# busfahrer_pi.net
KiCad netlist of a schematic drawn in EAGLE
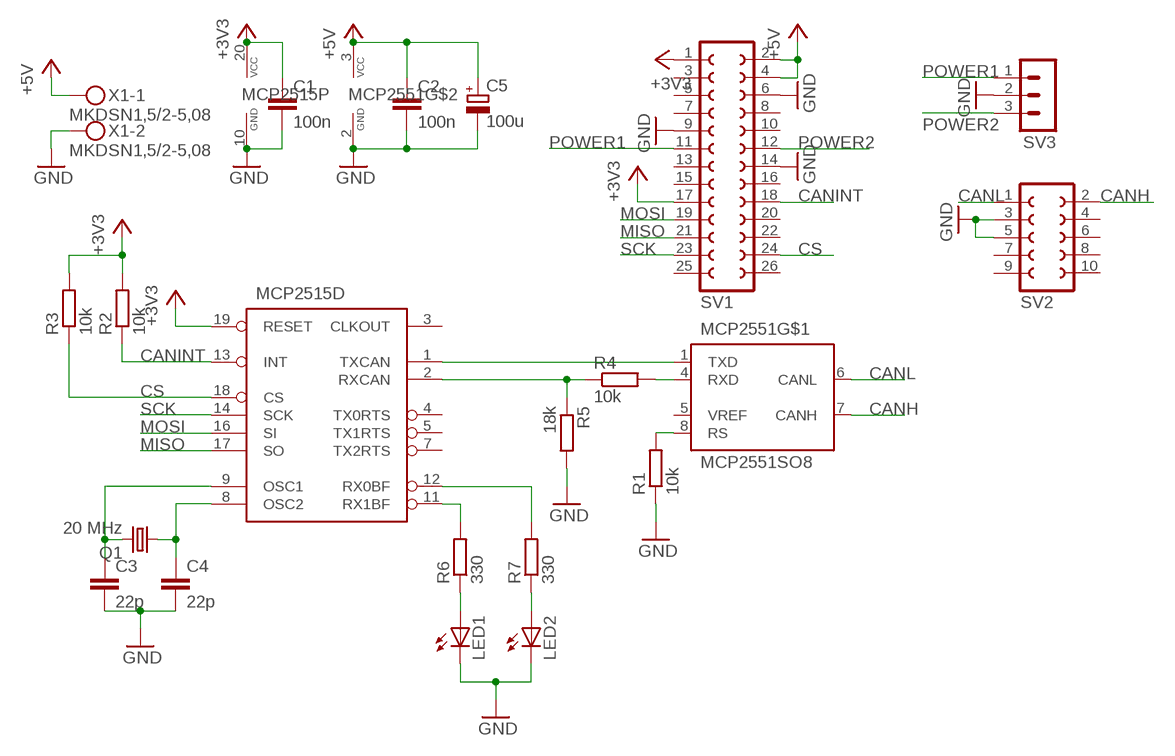
[diagram p0: schematic, sheet 1]

(export (version "E")
  (design (tool "Eeschema 10.0.6"))
  (components
    (comp (ref "C1")
      (value "100n")
      (footprint "eagle-import:C0805")
      (libsource (lib "eagle-import") (part "C-EUC0805"))
    )
    (comp (ref "C2")
      (value "100n")
      (footprint "eagle-import:C0805")
      (libsource (lib "eagle-import") (part "C-EUC0805"))
    )
    (comp (ref "C3")
      (value "22p")
      (footprint "eagle-import:C0805")
      (libsource (lib "eagle-import") (part "C-EUC0805"))
    )
    (comp (ref "C4")
      (value "22p")
      (footprint "eagle-import:C0805")
      (libsource (lib "eagle-import") (part "C-EUC0805"))
    )
    (comp (ref "C5")
      (value "100u")
      (footprint "eagle-import:E2,5-6")
      (libsource (lib "eagle-import") (part "CPOL-EUE2.5-6"))
    )
    (comp (ref "LED1")
      (value "LEDCHIP-LED0805")
      (footprint "eagle-import:CHIP-LED0805")
      (libsource (lib "eagle-import") (part "LEDCHIP-LED0805"))
    )
    (comp (ref "LED2")
      (value "LEDCHIP-LED0805")
      (footprint "eagle-import:CHIP-LED0805")
      (libsource (lib "eagle-import") (part "LEDCHIP-LED0805"))
    )
    (comp (ref "MCP2515")
      (value "MCP2515ST")
      (footprint "eagle-import:TSSOP20")
      (libsource (lib "eagle-import") (part "MCP2515ST"))
    )
    (comp (ref "MCP2551")
      (value "MCP2551SO8")
      (footprint "eagle-import:SO08")
      (libsource (lib "eagle-import") (part "MCP2551SO8"))
    )
    (comp (ref "Q1")
      (value "20 MHz")
      (footprint "eagle-import:HC49_S")
      (libsource (lib "eagle-import") (part "CRYSTALHC49S"))
    )
    (comp (ref "R1")
      (value "10k")
      (footprint "eagle-import:R0805")
      (libsource (lib "eagle-import") (part "R-EU_R0805"))
    )
    (comp (ref "R2")
      (value "10k")
      (footprint "eagle-import:R0805")
      (libsource (lib "eagle-import") (part "R-EU_R0805"))
    )
    (comp (ref "R3")
      (value "10k")
      (footprint "eagle-import:R0805")
      (libsource (lib "eagle-import") (part "R-EU_R0805"))
    )
    (comp (ref "R4")
      (value "10k")
      (footprint "eagle-import:R0805")
      (libsource (lib "eagle-import") (part "rcl_patch_R-EU_R0805"))
    )
    (comp (ref "R5")
      (value "18k")
      (footprint "eagle-import:R0805")
      (libsource (lib "eagle-import") (part "R-EU_R0805"))
    )
    (comp (ref "R6")
      (value "330")
      (footprint "eagle-import:R0805")
      (libsource (lib "eagle-import") (part "R-EU_R0805"))
    )
    (comp (ref "R7")
      (value "330")
      (footprint "eagle-import:R0805")
      (libsource (lib "eagle-import") (part "R-EU_R0805"))
    )
    (comp (ref "SV1")
      (value "FE13-2")
      (footprint "eagle-import:FE13-2")
      (libsource (lib "eagle-import") (part "FE13-2"))
    )
    (comp (ref "SV2")
      (value "FE05-2")
      (footprint "eagle-import:FE05-2")
      (libsource (lib "eagle-import") (part "FE05-2"))
    )
    (comp (ref "SV3")
      (value "MA03-1")
      (footprint "eagle-import:MA03-1")
      (libsource (lib "eagle-import") (part "MA03-1"))
    )
    (comp (ref "X1")
      (value "MKDSN1,5/2-5,08")
      (footprint "eagle-import:MKDSN1,5_2-5,08")
      (fields (field (name "MPN") "MKDSN 1,5/2-5.08"))
      (libsource (lib "eagle-import") (part "MKDSN1,5/2-5,08"))
    )
  )
  (nets
    (net (code "1") (name "+3V3") (class "Default")
      (node (ref "C1") (pin "1") (pinfunction "1_1") (pintype "passive"))
      (node (ref "MCP2515") (pin "19") (pinfunction "RESET_19") (pintype "input"))
      (node (ref "MCP2515") (pin "20") (pinfunction "VCC_20") (pintype "power_in"))
      (node (ref "R2") (pin "2") (pinfunction "2_2") (pintype "passive"))
      (node (ref "R3") (pin "2") (pinfunction "2_2") (pintype "passive"))
      (node (ref "SV1") (pin "1") (pinfunction "1_1") (pintype "passive"))
      (node (ref "SV1") (pin "17") (pinfunction "17_17") (pintype "passive"))
    )
    (net (code "2") (name "+5V") (class "Default")
      (node (ref "C2") (pin "1") (pinfunction "1_1") (pintype "passive"))
      (node (ref "C5") (pin "+") (pinfunction "+_+") (pintype "passive"))
      (node (ref "MCP2551") (pin "3") (pinfunction "VCC_3") (pintype "power_in"))
      (node (ref "SV1") (pin "2") (pinfunction "2_2") (pintype "passive"))
      (node (ref "SV1") (pin "4") (pinfunction "4_4") (pintype "passive"))
      (node (ref "X1") (pin "1") (pinfunction "KL_1") (pintype "passive"))
    )
    (net (code "3") (name "/CANH") (class "Default")
      (node (ref "MCP2551") (pin "7") (pinfunction "CANH_7") (pintype "bidirectional"))
      (node (ref "SV2") (pin "2") (pinfunction "2_2") (pintype "passive"))
    )
    (net (code "4") (name "/CANINT") (class "Default")
      (node (ref "MCP2515") (pin "13") (pinfunction "INT_13") (pintype "output"))
      (node (ref "R2") (pin "1") (pinfunction "1_1") (pintype "passive"))
      (node (ref "SV1") (pin "18") (pinfunction "18_18") (pintype "passive"))
    )
    (net (code "5") (name "/CANL") (class "Default")
      (node (ref "MCP2551") (pin "6") (pinfunction "CANL_6") (pintype "bidirectional"))
      (node (ref "SV2") (pin "1") (pinfunction "1_1") (pintype "passive"))
    )
    (net (code "6") (name "/CS") (class "Default")
      (node (ref "MCP2515") (pin "18") (pinfunction "CS_18") (pintype "input"))
      (node (ref "R3") (pin "1") (pinfunction "1_1") (pintype "passive"))
      (node (ref "SV1") (pin "24") (pinfunction "24_24") (pintype "passive"))
    )
    (net (code "7") (name "/MISO") (class "Default")
      (node (ref "MCP2515") (pin "17") (pinfunction "SO_17") (pintype "output"))
      (node (ref "SV1") (pin "21") (pinfunction "21_21") (pintype "passive"))
    )
    (net (code "8") (name "/MOSI") (class "Default")
      (node (ref "MCP2515") (pin "16") (pinfunction "SI_16") (pintype "input"))
      (node (ref "SV1") (pin "19") (pinfunction "19_19") (pintype "passive"))
    )
    (net (code "9") (name "/POWER1") (class "Default")
      (node (ref "SV1") (pin "11") (pinfunction "11_11") (pintype "passive"))
      (node (ref "SV3") (pin "1") (pinfunction "1_1") (pintype "passive"))
    )
    (net (code "10") (name "/POWER2") (class "Default")
      (node (ref "SV1") (pin "12") (pinfunction "12_12") (pintype "passive"))
      (node (ref "SV3") (pin "3") (pinfunction "3_3") (pintype "passive"))
    )
    (net (code "11") (name "/SCK") (class "Default")
      (node (ref "MCP2515") (pin "14") (pinfunction "SCK_14") (pintype "input"))
      (node (ref "SV1") (pin "23") (pinfunction "23_23") (pintype "passive"))
    )
    (net (code "12") (name "GND") (class "Default")
      (node (ref "C1") (pin "2") (pinfunction "2_2") (pintype "passive"))
      (node (ref "C2") (pin "2") (pinfunction "2_2") (pintype "passive"))
      (node (ref "C3") (pin "2") (pinfunction "2_2") (pintype "passive"))
      (node (ref "C4") (pin "2") (pinfunction "2_2") (pintype "passive"))
      (node (ref "C5") (pin "-") (pinfunction "-_-") (pintype "passive"))
      (node (ref "LED1") (pin "C") (pinfunction "C_C") (pintype "passive"))
      (node (ref "LED2") (pin "C") (pinfunction "C_C") (pintype "passive"))
      (node (ref "MCP2515") (pin "10") (pinfunction "GND_10") (pintype "power_in"))
      (node (ref "MCP2551") (pin "2") (pinfunction "GND_2") (pintype "power_in"))
      (node (ref "R1") (pin "1") (pinfunction "1_1") (pintype "passive"))
      (node (ref "R5") (pin "2") (pinfunction "2_2") (pintype "passive"))
      (node (ref "SV1") (pin "14") (pinfunction "14_14") (pintype "passive"))
      (node (ref "SV1") (pin "6") (pinfunction "6_6") (pintype "passive"))
      (node (ref "SV1") (pin "9") (pinfunction "9_9") (pintype "passive"))
      (node (ref "SV2") (pin "3") (pinfunction "3_3") (pintype "passive"))
      (node (ref "SV2") (pin "5") (pinfunction "5_5") (pintype "passive"))
      (node (ref "SV3") (pin "2") (pinfunction "2_2") (pintype "passive"))
      (node (ref "X1") (pin "2") (pinfunction "KL_2") (pintype "passive"))
    )
    (net (code "13") (name "Net-(LED1-PadA)") (class "Default")
      (node (ref "LED1") (pin "A") (pinfunction "A_A") (pintype "passive"))
      (node (ref "R6") (pin "1") (pinfunction "1_1") (pintype "passive"))
    )
    (net (code "14") (name "Net-(LED2-PadA)") (class "Default")
      (node (ref "LED2") (pin "A") (pinfunction "A_A") (pintype "passive"))
      (node (ref "R7") (pin "1") (pinfunction "1_1") (pintype "passive"))
    )
    (net (code "15") (name "Net-(MCP2515A-OSC1)") (class "Default")
      (node (ref "C3") (pin "1") (pinfunction "1_1") (pintype "passive"))
      (node (ref "MCP2515") (pin "9") (pinfunction "OSC1_9") (pintype "input"))
      (node (ref "Q1") (pin "2") (pinfunction "2_2") (pintype "passive"))
    )
    (net (code "16") (name "Net-(MCP2515A-OSC2)") (class "Default")
      (node (ref "C4") (pin "1") (pinfunction "1_1") (pintype "passive"))
      (node (ref "MCP2515") (pin "8") (pinfunction "OSC2_8") (pintype "input"))
      (node (ref "Q1") (pin "1") (pinfunction "1_1") (pintype "passive"))
    )
    (net (code "17") (name "Net-(MCP2515A-RX0BF)") (class "Default")
      (node (ref "MCP2515") (pin "12") (pinfunction "RX0BF_12") (pintype "output"))
      (node (ref "R7") (pin "2") (pinfunction "2_2") (pintype "passive"))
    )
    (net (code "18") (name "Net-(MCP2515A-RX1BF)") (class "Default")
      (node (ref "MCP2515") (pin "11") (pinfunction "RX1BF_11") (pintype "output"))
      (node (ref "R6") (pin "2") (pinfunction "2_2") (pintype "passive"))
    )
    (net (code "19") (name "Net-(MCP2515A-RXCAN)") (class "Default")
      (node (ref "MCP2515") (pin "2") (pinfunction "RXCAN_2") (pintype "input"))
      (node (ref "R4") (pin "1") (pinfunction "1_1") (pintype "passive"))
      (node (ref "R5") (pin "1") (pinfunction "1_1") (pintype "passive"))
    )
    (net (code "20") (name "Net-(MCP2515A-TXCAN)") (class "Default")
      (node (ref "MCP2515") (pin "1") (pinfunction "TXCAN_1") (pintype "output"))
      (node (ref "MCP2551") (pin "1") (pinfunction "TXD_1") (pintype "bidirectional"))
    )
    (net (code "21") (name "Net-(MCP2551A-RS)") (class "Default")
      (node (ref "MCP2551") (pin "8") (pinfunction "RS_8") (pintype "bidirectional"))
      (node (ref "R1") (pin "2") (pinfunction "2_2") (pintype "passive"))
    )
    (net (code "22") (name "Net-(MCP2551A-RXD)") (class "Default")
      (node (ref "MCP2551") (pin "4") (pinfunction "RXD_4") (pintype "bidirectional"))
      (node (ref "R4") (pin "2") (pinfunction "2_2") (pintype "passive"))
    )
    (net (code "23") (name "unconnected-(MCP2515A-CLKOUT-Pad3)") (class "Default")
      (node (ref "MCP2515") (pin "3") (pinfunction "CLKOUT_3") (pintype "output"))
    )
    (net (code "24") (name "unconnected-(MCP2515A-TX0RTS-Pad4)") (class "Default")
      (node (ref "MCP2515") (pin "4") (pinfunction "TX0RTS_4") (pintype "input"))
    )
    (net (code "25") (name "unconnected-(MCP2515A-TX1RTS-Pad5)") (class "Default")
      (node (ref "MCP2515") (pin "5") (pinfunction "TX1RTS_5") (pintype "input"))
    )
    (net (code "26") (name "unconnected-(MCP2515A-TX2RTS-Pad7)") (class "Default")
      (node (ref "MCP2515") (pin "7") (pinfunction "TX2RTS_7") (pintype "input"))
    )
    (net (code "27") (name "unconnected-(MCP2551A-VREF-Pad5)") (class "Default")
      (node (ref "MCP2551") (pin "5") (pinfunction "VREF_5") (pintype "bidirectional"))
    )
    (net (code "28") (name "unconnected-(SV1-Pad3)") (class "Default")
      (node (ref "SV1") (pin "3") (pinfunction "3_3") (pintype "passive"))
    )
    (net (code "29") (name "unconnected-(SV1-Pad5)") (class "Default")
      (node (ref "SV1") (pin "5") (pinfunction "5_5") (pintype "passive"))
    )
    (net (code "30") (name "unconnected-(SV1-Pad7)") (class "Default")
      (node (ref "SV1") (pin "7") (pinfunction "7_7") (pintype "passive"))
    )
    (net (code "31") (name "unconnected-(SV1-Pad8)") (class "Default")
      (node (ref "SV1") (pin "8") (pinfunction "8_8") (pintype "passive"))
    )
    (net (code "32") (name "unconnected-(SV1-Pad10)") (class "Default")
      (node (ref "SV1") (pin "10") (pinfunction "10_10") (pintype "passive"))
    )
    (net (code "33") (name "unconnected-(SV1-Pad13)") (class "Default")
      (node (ref "SV1") (pin "13") (pinfunction "13_13") (pintype "passive"))
    )
    (net (code "34") (name "unconnected-(SV1-Pad15)") (class "Default")
      (node (ref "SV1") (pin "15") (pinfunction "15_15") (pintype "passive"))
    )
    (net (code "35") (name "unconnected-(SV1-Pad16)") (class "Default")
      (node (ref "SV1") (pin "16") (pinfunction "16_16") (pintype "passive"))
    )
    (net (code "36") (name "unconnected-(SV1-Pad20)") (class "Default")
      (node (ref "SV1") (pin "20") (pinfunction "20_20") (pintype "passive"))
    )
    (net (code "37") (name "unconnected-(SV1-Pad22)") (class "Default")
      (node (ref "SV1") (pin "22") (pinfunction "22_22") (pintype "passive"))
    )
    (net (code "38") (name "unconnected-(SV1-Pad25)") (class "Default")
      (node (ref "SV1") (pin "25") (pinfunction "25_25") (pintype "passive"))
    )
    (net (code "39") (name "unconnected-(SV1-Pad26)") (class "Default")
      (node (ref "SV1") (pin "26") (pinfunction "26_26") (pintype "passive"))
    )
    (net (code "40") (name "unconnected-(SV2-Pad4)") (class "Default")
      (node (ref "SV2") (pin "4") (pinfunction "4_4") (pintype "passive"))
    )
    (net (code "41") (name "unconnected-(SV2-Pad6)") (class "Default")
      (node (ref "SV2") (pin "6") (pinfunction "6_6") (pintype "passive"))
    )
    (net (code "42") (name "unconnected-(SV2-Pad7)") (class "Default")
      (node (ref "SV2") (pin "7") (pinfunction "7_7") (pintype "passive"))
    )
    (net (code "43") (name "unconnected-(SV2-Pad8)") (class "Default")
      (node (ref "SV2") (pin "8") (pinfunction "8_8") (pintype "passive"))
    )
    (net (code "44") (name "unconnected-(SV2-Pad9)") (class "Default")
      (node (ref "SV2") (pin "9") (pinfunction "9_9") (pintype "passive"))
    )
    (net (code "45") (name "unconnected-(SV2-Pad10)") (class "Default")
      (node (ref "SV2") (pin "10") (pinfunction "10_10") (pintype "passive"))
    )
  )
)
